# Sheet1.net
KiCad netlist of a schematic drawn in Altium Designer
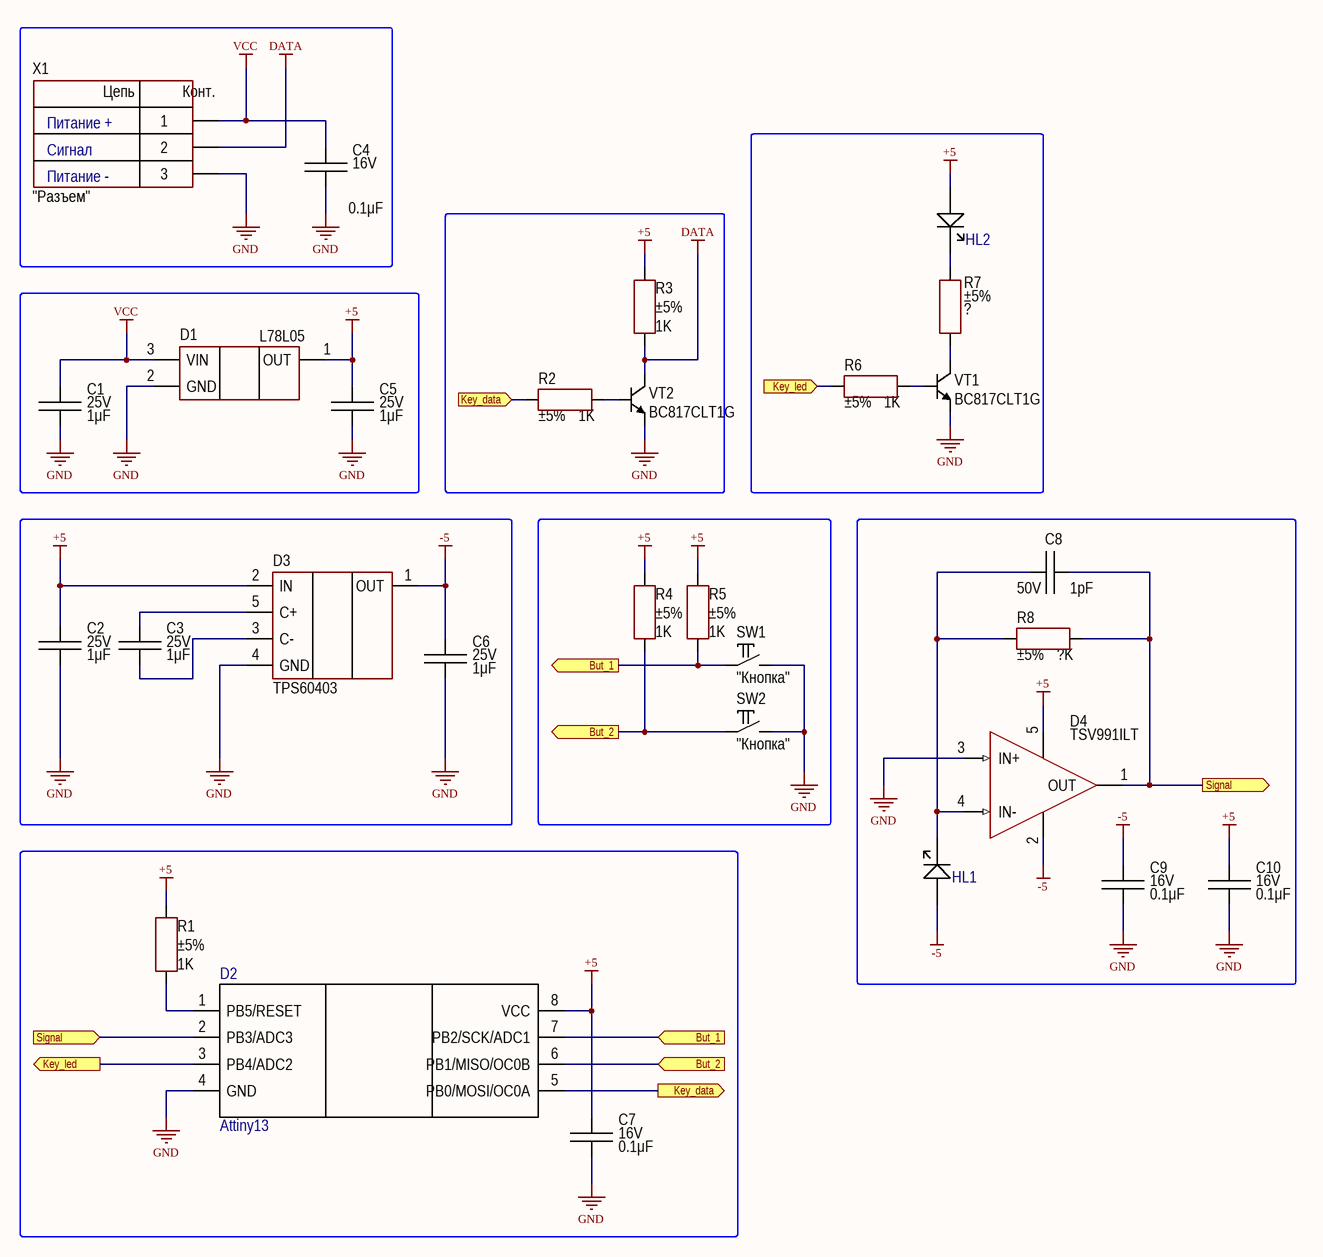
[diagram p0: Sheet1.SchDoc]

(export (version "E")
  (design (tool "Eeschema 10.0.6"))
  (components
    (comp (ref "C1")
      (value "1μF")
      (footprint "CAP: 0603")
      (fields
        (field (name "MANUFACTURER") "Yageo")
        (field (name "PARTNUMBER") "CC0603KRX7R7BB104")
        (field (name "VALUEMANUFACTURERPARTNUMBER") "Ceramic capacitor, 1μF, X7R, ±10%, 25V, 0603, -55...+125°C")
        (field (name "VOLTAGE") "25V")
      )
      (libsource (lib "capacitor") (part "Ceramic_0603"))
    )
    (comp (ref "C2")
      (value "1μF")
      (footprint "CAP: 0603")
      (fields
        (field (name "MANUFACTURER") "Yageo")
        (field (name "PARTNUMBER") "CC0603KRX7R7BB104")
        (field (name "VALUEMANUFACTURERPARTNUMBER") "Ceramic capacitor, 1μF, X7R, ±10%, 25V, 0603, -55...+125°C")
        (field (name "VOLTAGE") "25V")
      )
      (libsource (lib "capacitor") (part "Ceramic_0603"))
    )
    (comp (ref "C3")
      (value "1μF")
      (footprint "CAP: 0603")
      (fields
        (field (name "MANUFACTURER") "Yageo")
        (field (name "PARTNUMBER") "CC0603KRX7R7BB104")
        (field (name "VALUEMANUFACTURERPARTNUMBER") "Ceramic capacitor, 1μF, X7R, ±10%, 25V, 0603, -55...+125°C")
        (field (name "VOLTAGE") "25V")
      )
      (libsource (lib "capacitor") (part "Ceramic_0603"))
    )
    (comp (ref "C4")
      (value "0.1μF")
      (footprint "CAP: 0603")
      (fields
        (field (name "MANUFACTURER") "Yageo")
        (field (name "PARTNUMBER") "CC0603KRX7R7BB104")
        (field (name "VALUEMANUFACTURERPARTNUMBER") "Ceramic capacitor, 0.1μF, X7R, ±10%, 16V, 0603, -55...+125°C")
        (field (name "VOLTAGE") "16V")
      )
      (libsource (lib "capacitor") (part "Ceramic_0603"))
    )
    (comp (ref "C5")
      (value "1μF")
      (footprint "CAP: 0603")
      (fields
        (field (name "MANUFACTURER") "Yageo")
        (field (name "PARTNUMBER") "CC0603KRX7R7BB104")
        (field (name "VALUEMANUFACTURERPARTNUMBER") "Ceramic capacitor, 1μF, X7R, ±10%, 25V, 0603, -55...+125°C")
        (field (name "VOLTAGE") "25V")
      )
      (libsource (lib "capacitor") (part "Ceramic_0603"))
    )
    (comp (ref "C6")
      (value "1μF")
      (footprint "CAP: 0603")
      (fields
        (field (name "MANUFACTURER") "Yageo")
        (field (name "PARTNUMBER") "CC0603KRX7R7BB104")
        (field (name "VALUEMANUFACTURERPARTNUMBER") "Ceramic capacitor, 1μF, X7R, ±10%, 25V, 0603, -55...+125°C")
        (field (name "VOLTAGE") "25V")
      )
      (libsource (lib "capacitor") (part "Ceramic_0603"))
    )
    (comp (ref "C7")
      (value "0.1μF")
      (footprint "CAP: 0603")
      (fields
        (field (name "MANUFACTURER") "Yageo")
        (field (name "PARTNUMBER") "CC0603KRX7R7BB104")
        (field (name "VALUEMANUFACTURERPARTNUMBER") "Ceramic capacitor, 0.1μF, X7R, ±10%, 16V, 0603, -55...+125°C")
        (field (name "VOLTAGE") "16V")
      )
      (libsource (lib "capacitor") (part "Ceramic_0603"))
    )
    (comp (ref "C8")
      (value "1pF")
      (footprint "CAP: 1206")
      (fields
        (field (name "MANUFACTURER") "Yageo")
        (field (name "PARTNUMBER") "CC1206KRX7R9BB104")
        (field (name "VALUEMANUFACTURERPARTNUMBER") "Ceramic capacitor, 1pF, X7R, ±10%, 50V, 1206, -55...+125°C")
        (field (name "VOLTAGE") "50V")
      )
      (libsource (lib "capacitor") (part "Ceramic_1206"))
    )
    (comp (ref "C9")
      (value "0.1μF")
      (footprint "CAP: 0603")
      (fields
        (field (name "MANUFACTURER") "Yageo")
        (field (name "PARTNUMBER") "CC0603KRX7R7BB104")
        (field (name "VALUEMANUFACTURERPARTNUMBER") "Ceramic capacitor, 0.1μF, X7R, ±10%, 16V, 0603, -55...+125°C")
        (field (name "VOLTAGE") "16V")
      )
      (libsource (lib "capacitor") (part "Ceramic_0603"))
    )
    (comp (ref "C10")
      (value "0.1μF")
      (footprint "CAP: 0603")
      (fields
        (field (name "MANUFACTURER") "Yageo")
        (field (name "PARTNUMBER") "CC0603KRX7R7BB104")
        (field (name "VALUEMANUFACTURERPARTNUMBER") "Ceramic capacitor, 0.1μF, X7R, ±10%, 16V, 0603, -55...+125°C")
        (field (name "VOLTAGE") "16V")
      )
      (libsource (lib "capacitor") (part "Ceramic_0603"))
    )
    (comp (ref "D1")
      (value "~")
      (footprint "SOT89")
      (description "Positive voltage regulators")
      (fields
        (field (name "VALUEMANUFACTURERPARTNUMBER") "Linear voltage regulator, input 3.9...18V, 0.6V, output 5V, 0.1A, -40...+85°C, SOT-89")
        (field (name "PARTNUMBER") "L78L05")
      )
      (libsource (lib "ic-power-supply") (part "L78L05"))
    )
    (comp (ref "D2")
      (value "Attiny13")
      (footprint "8-SOIC")
      (libsource (lib "Main_Lib") (part "ATtiny13 SO-8"))
    )
    (comp (ref "D3")
      (value "~")
      (footprint "SOT23-5")
      (description "Voltage Inverter")
      (fields
        (field (name "VALUEMANUFACTURERPARTNUMBER") ", , , , , -40...+150°C, SOT23-5")
        (field (name "PARTNUMBER") "TPS60403")
      )
      (libsource (lib "ic-power-supply") (part "TPS60403"))
    )
    (comp (ref "D4")
      (value "~")
      (footprint "SOT23-5")
      (description "OP amplifier")
      (fields
        (field (name "MANUFACTURER") "STMicroelectronics")
        (field (name "VALUEMANUFACTURERPARTNUMBER") "IC op amplifier, Rail-to-Rail, 20 MHz, 2.7...5.5V, -40...+125°C, SOT23-5")
        (field (name "PARTNUMBER") "TSV991ILT")
      )
      (libsource (lib "ic-amplifier") (part "AD8541ARZ"))
    )
    (comp (ref "HL1")
      (value "*")
      (footprint "LED: 5mm (H:0mm)(blue)")
      (libsource (lib "Main_Lib") (part "Led"))
    )
    (comp (ref "HL2")
      (value "*")
      (footprint "LED: 5mm (H:0mm)(red)")
      (libsource (lib "Main_Lib") (part "Led"))
    )
    (comp (ref "R1")
      (value "1K")
      (footprint "RES: 0603")
      (fields
        (field (name "MANUFACTURER") "Yageo")
        (field (name "PARTNUMBER") "RC0603JR-07100RL")
        (field (name "VALUEMANUFACTURERPARTNUMBER") "Resistor film, 1K, ±5%, 0603, 0.1W, -55...+125°C")
        (field (name "TOLERANCE") "±5%")
      )
      (libsource (lib "resistor") (part "Resistor_0603"))
    )
    (comp (ref "R2")
      (value "1K")
      (footprint "RES: 0603")
      (fields
        (field (name "MANUFACTURER") "Yageo")
        (field (name "PARTNUMBER") "RC0603JR-07100RL")
        (field (name "VALUEMANUFACTURERPARTNUMBER") "Resistor film, 1K, ±5%, 0603, 0.1W, -55...+125°C")
        (field (name "TOLERANCE") "±5%")
      )
      (libsource (lib "resistor") (part "Resistor_0603"))
    )
    (comp (ref "R3")
      (value "1K")
      (footprint "RES: 0603")
      (fields
        (field (name "MANUFACTURER") "Yageo")
        (field (name "PARTNUMBER") "RC0603JR-07100RL")
        (field (name "VALUEMANUFACTURERPARTNUMBER") "Resistor film, 1K, ±5%, 0603, 0.1W, -55...+125°C")
        (field (name "TOLERANCE") "±5%")
      )
      (libsource (lib "") (part "Resistor_0603_2"))
    )
    (comp (ref "R4")
      (value "1K")
      (footprint "RES: 0603")
      (fields
        (field (name "MANUFACTURER") "Yageo")
        (field (name "PARTNUMBER") "RC0603JR-07100RL")
        (field (name "VALUEMANUFACTURERPARTNUMBER") "Resistor film, 1K, ±5%, 0603, 0.1W, -55...+125°C")
        (field (name "TOLERANCE") "±5%")
      )
      (libsource (lib "") (part "Resistor_0603_2"))
    )
    (comp (ref "R5")
      (value "1K")
      (footprint "RES: 0603")
      (fields
        (field (name "MANUFACTURER") "Yageo")
        (field (name "PARTNUMBER") "RC0603JR-07100RL")
        (field (name "VALUEMANUFACTURERPARTNUMBER") "Resistor film, 1K, ±5%, 0603, 0.1W, -55...+125°C")
        (field (name "TOLERANCE") "±5%")
      )
      (libsource (lib "") (part "Resistor_0603_2"))
    )
    (comp (ref "R6")
      (value "1K")
      (footprint "RES: 0603")
      (fields
        (field (name "MANUFACTURER") "Yageo")
        (field (name "PARTNUMBER") "RC0603JR-07100RL")
        (field (name "VALUEMANUFACTURERPARTNUMBER") "Resistor film, 1K, ±5%, 0603, 0.1W, -55...+125°C")
        (field (name "TOLERANCE") "±5%")
      )
      (libsource (lib "resistor") (part "Resistor_0603"))
    )
    (comp (ref "R7")
      (value "?")
      (footprint "RES: 0603")
      (fields
        (field (name "MANUFACTURER") "Yageo")
        (field (name "PARTNUMBER") "RC0603JR-07100RL")
        (field (name "VALUEMANUFACTURERPARTNUMBER") "Resistor film, ?, ±5%, 0603, 0.1W, -55...+125°C")
        (field (name "TOLERANCE") "±5%")
      )
      (libsource (lib "") (part "Resistor_0603_1"))
    )
    (comp (ref "R8")
      (value "?K")
      (footprint "RES: 1206")
      (fields
        (field (name "MANUFACTURER") "Yageo")
        (field (name "PARTNUMBER") "RC1206JR-07100RL")
        (field (name "VALUEMANUFACTURERPARTNUMBER") "Resistor film, ?K, ±5%, 1206, 0.25W, -55...+125°C")
        (field (name "TOLERANCE") "±5%")
      )
      (libsource (lib "resistor") (part "Resistor_1206"))
    )
    (comp (ref "SW1")
      (value "~")
      (footprint "BUT: 3x4x2 SMT")
      (description "SMT 3*4*2 2PIN")
      (fields
        (field (name "MANUFACTURER") "xin cheng electronic")
        (field (name "VALUEMANUFACTURERPARTNUMBER") ", 3*4*2mm")
        (field (name "COMMENTTEXT") "\"Кнопка\"")
      )
      (libsource (lib "electromechanics") (part "Button_3x4x2_SMT"))
    )
    (comp (ref "SW2")
      (value "~")
      (footprint "BUT: 3x4x2 SMT")
      (description "SMT 3*4*2 2PIN")
      (fields
        (field (name "MANUFACTURER") "xin cheng electronic")
        (field (name "VALUEMANUFACTURERPARTNUMBER") ", 3*4*2mm")
        (field (name "COMMENTTEXT") "\"Кнопка\"")
      )
      (libsource (lib "electromechanics") (part "Button_3x4x2_SMT"))
    )
    (comp (ref "VT1")
      (value "~")
      (footprint "SC-70")
      (fields
        (field (name "MANUFACTURER") "ON Semiconductor")
        (field (name "VALUEMANUFACTURERPARTNUMBER") "NPN transistor, 45V, 100mA, 100MHz, 300mW, 0.6V, 420, SOT-23, -55...+125°C")
        (field (name "PARTNUMBER") "BC817CLT1G")
      )
      (libsource (lib "Main_Lib") (part "Bipolar_NPN"))
    )
    (comp (ref "VT2")
      (value "~")
      (footprint "SC-70")
      (fields
        (field (name "MANUFACTURER") "ON Semiconductor")
        (field (name "VALUEMANUFACTURERPARTNUMBER") "NPN transistor, 45V, 100mA, 100MHz, 300mW, 0.6V, 420, SOT-23, -55...+125°C")
        (field (name "PARTNUMBER") "BC817CLT1G")
      )
      (libsource (lib "Main_Lib") (part "Bipolar_NPN"))
    )
    (comp (ref "X1")
      (value "~")
      (footprint "CON: PLS-3")
      (fields
        (field (name "MANUFACTURER") "Connfly")
        (field (name "VALUEMANUFACTURERPARTNUMBER") "Connector, 3pin, 2.54mm, 500VAC, 3A")
        (field (name "PARTNUMBER") "PLS-3")
        (field (name "COMMENTTEXT") "\"Разъем\"")
      )
      (libsource (lib "Main_Lib") (part "PLS-3"))
    )
  )
  (nets
    (net (code "1") (name "+5") (class "Default")
      (node (ref "C10") (pin "2") (pinfunction "2_2") (pintype "passive"))
      (node (ref "C2") (pin "2") (pinfunction "2_2") (pintype "passive"))
      (node (ref "C5") (pin "2") (pinfunction "2_2") (pintype "passive"))
      (node (ref "C7") (pin "2") (pinfunction "2_2") (pintype "passive"))
      (node (ref "D1") (pin "1") (pinfunction "OUT_1") (pintype "power_in"))
      (node (ref "D2") (pin "8") (pinfunction "VCC_8") (pintype "passive"))
      (node (ref "D3") (pin "2") (pinfunction "IN_2") (pintype "passive"))
      (node (ref "D4") (pin "5") (pinfunction "V+_5") (pintype "power_in"))
      (node (ref "HL2") (pin "2") (pintype "passive"))
      (node (ref "R1") (pin "1") (pinfunction "1_1") (pintype "passive"))
      (node (ref "R3") (pin "1") (pinfunction "1_1") (pintype "passive"))
      (node (ref "R4") (pin "1") (pinfunction "1_1") (pintype "passive"))
      (node (ref "R5") (pin "1") (pinfunction "1_1") (pintype "passive"))
    )
    (net (code "2") (name "-5") (class "Default")
      (node (ref "C6") (pin "2") (pinfunction "2_2") (pintype "passive"))
      (node (ref "C9") (pin "2") (pinfunction "2_2") (pintype "passive"))
      (node (ref "D3") (pin "1") (pinfunction "OUT_1") (pintype "passive"))
      (node (ref "D4") (pin "2") (pinfunction "V-_2") (pintype "power_in"))
      (node (ref "HL1") (pin "2") (pintype "passive"))
    )
    (net (code "3") (name "/But_1") (class "Default")
      (node (ref "D2") (pin "7") (pinfunction "PB2/SCK/ADC1_7") (pintype "passive"))
      (node (ref "R5") (pin "2") (pinfunction "2_2") (pintype "passive"))
      (node (ref "SW1") (pin "1") (pinfunction "1_1") (pintype "passive"))
    )
    (net (code "4") (name "/But_2") (class "Default")
      (node (ref "D2") (pin "6") (pinfunction "PB1/MISO/OC0B_6") (pintype "passive"))
      (node (ref "R4") (pin "2") (pinfunction "2_2") (pintype "passive"))
      (node (ref "SW2") (pin "1") (pinfunction "1_1") (pintype "passive"))
    )
    (net (code "5") (name "/Key_data") (class "Default")
      (node (ref "D2") (pin "5") (pinfunction "PB0/MOSI/OC0A_5") (pintype "passive"))
      (node (ref "R2") (pin "2") (pinfunction "2_2") (pintype "passive"))
    )
    (net (code "6") (name "/Key_led") (class "Default")
      (node (ref "D2") (pin "3") (pinfunction "PB4/ADC2_3") (pintype "passive"))
      (node (ref "R6") (pin "2") (pinfunction "2_2") (pintype "passive"))
    )
    (net (code "7") (name "/Signal") (class "Default")
      (node (ref "C8") (pin "1") (pinfunction "1_1") (pintype "passive"))
      (node (ref "D2") (pin "2") (pinfunction "PB3/ADC3_2") (pintype "passive"))
      (node (ref "D4") (pin "1") (pinfunction "OUT_1") (pintype "power_in"))
      (node (ref "R8") (pin "2") (pinfunction "2_2") (pintype "passive"))
    )
    (net (code "8") (name "DATA") (class "Default")
      (node (ref "R3") (pin "2") (pinfunction "2_2") (pintype "passive"))
      (node (ref "VT2") (pin "3") (pinfunction "C_3") (pintype "passive"))
      (node (ref "X1") (pin "2") (pinfunction "2_2") (pintype "passive"))
    )
    (net (code "9") (name "GND") (class "Default")
      (node (ref "C1") (pin "1") (pinfunction "1_1") (pintype "passive"))
      (node (ref "C10") (pin "1") (pinfunction "1_1") (pintype "passive"))
      (node (ref "C2") (pin "1") (pinfunction "1_1") (pintype "passive"))
      (node (ref "C4") (pin "1") (pinfunction "1_1") (pintype "passive"))
      (node (ref "C5") (pin "1") (pinfunction "1_1") (pintype "passive"))
      (node (ref "C6") (pin "1") (pinfunction "1_1") (pintype "passive"))
      (node (ref "C7") (pin "1") (pinfunction "1_1") (pintype "passive"))
      (node (ref "C9") (pin "1") (pinfunction "1_1") (pintype "passive"))
      (node (ref "D1") (pin "2") (pinfunction "GND_2") (pintype "power_in"))
      (node (ref "D2") (pin "4") (pinfunction "GND_4") (pintype "passive"))
      (node (ref "D3") (pin "4") (pinfunction "GND_4") (pintype "passive"))
      (node (ref "D4") (pin "3") (pinfunction "IN+_3") (pintype "input"))
      (node (ref "SW1") (pin "2") (pinfunction "2_2") (pintype "passive"))
      (node (ref "SW2") (pin "2") (pinfunction "2_2") (pintype "passive"))
      (node (ref "VT1") (pin "2") (pinfunction "E_2") (pintype "passive"))
      (node (ref "VT2") (pin "2") (pinfunction "E_2") (pintype "passive"))
      (node (ref "X1") (pin "3") (pinfunction "3_3") (pintype "power_in"))
    )
    (net (code "10") (name "Net-(D2-PB5{slash}RESET)") (class "Default")
      (node (ref "D2") (pin "1") (pinfunction "PB5/RESET_1") (pintype "passive"))
      (node (ref "R1") (pin "2") (pinfunction "2_2") (pintype "passive"))
    )
    (net (code "11") (name "Net-(D3-C+)") (class "Default")
      (node (ref "C3") (pin "2") (pinfunction "2_2") (pintype "passive"))
      (node (ref "D3") (pin "5") (pinfunction "C+_5") (pintype "passive"))
    )
    (net (code "12") (name "Net-(D3-C-)") (class "Default")
      (node (ref "C3") (pin "1") (pinfunction "1_1") (pintype "passive"))
      (node (ref "D3") (pin "3") (pinfunction "C-_3") (pintype "passive"))
    )
    (net (code "13") (name "Net-(D4-IN-)") (class "Default")
      (node (ref "C8") (pin "2") (pinfunction "2_2") (pintype "passive"))
      (node (ref "D4") (pin "4") (pinfunction "IN-_4") (pintype "input"))
      (node (ref "HL1") (pin "1") (pintype "passive"))
      (node (ref "R8") (pin "1") (pinfunction "1_1") (pintype "passive"))
    )
    (net (code "14") (name "Net-(HL2-Pad1)") (class "Default")
      (node (ref "HL2") (pin "1") (pintype "passive"))
      (node (ref "R7") (pin "2") (pinfunction "2_2") (pintype "passive"))
    )
    (net (code "15") (name "Net-(VT1-B)") (class "Default")
      (node (ref "R6") (pin "1") (pinfunction "1_1") (pintype "passive"))
      (node (ref "VT1") (pin "1") (pinfunction "B_1") (pintype "passive"))
    )
    (net (code "16") (name "Net-(VT1-C)") (class "Default")
      (node (ref "R7") (pin "1") (pinfunction "1_1") (pintype "passive"))
      (node (ref "VT1") (pin "3") (pinfunction "C_3") (pintype "passive"))
    )
    (net (code "17") (name "Net-(VT2-B)") (class "Default")
      (node (ref "R2") (pin "1") (pinfunction "1_1") (pintype "passive"))
      (node (ref "VT2") (pin "1") (pinfunction "B_1") (pintype "passive"))
    )
    (net (code "18") (name "VCC") (class "Default")
      (node (ref "C1") (pin "2") (pinfunction "2_2") (pintype "passive"))
      (node (ref "C4") (pin "2") (pinfunction "2_2") (pintype "passive"))
      (node (ref "D1") (pin "3") (pinfunction "VIN_3") (pintype "power_in"))
      (node (ref "X1") (pin "1") (pinfunction "1_1") (pintype "passive"))
    )
  )
)
